# CAN.net
KiCad netlist of a schematic drawn in Altium Designer
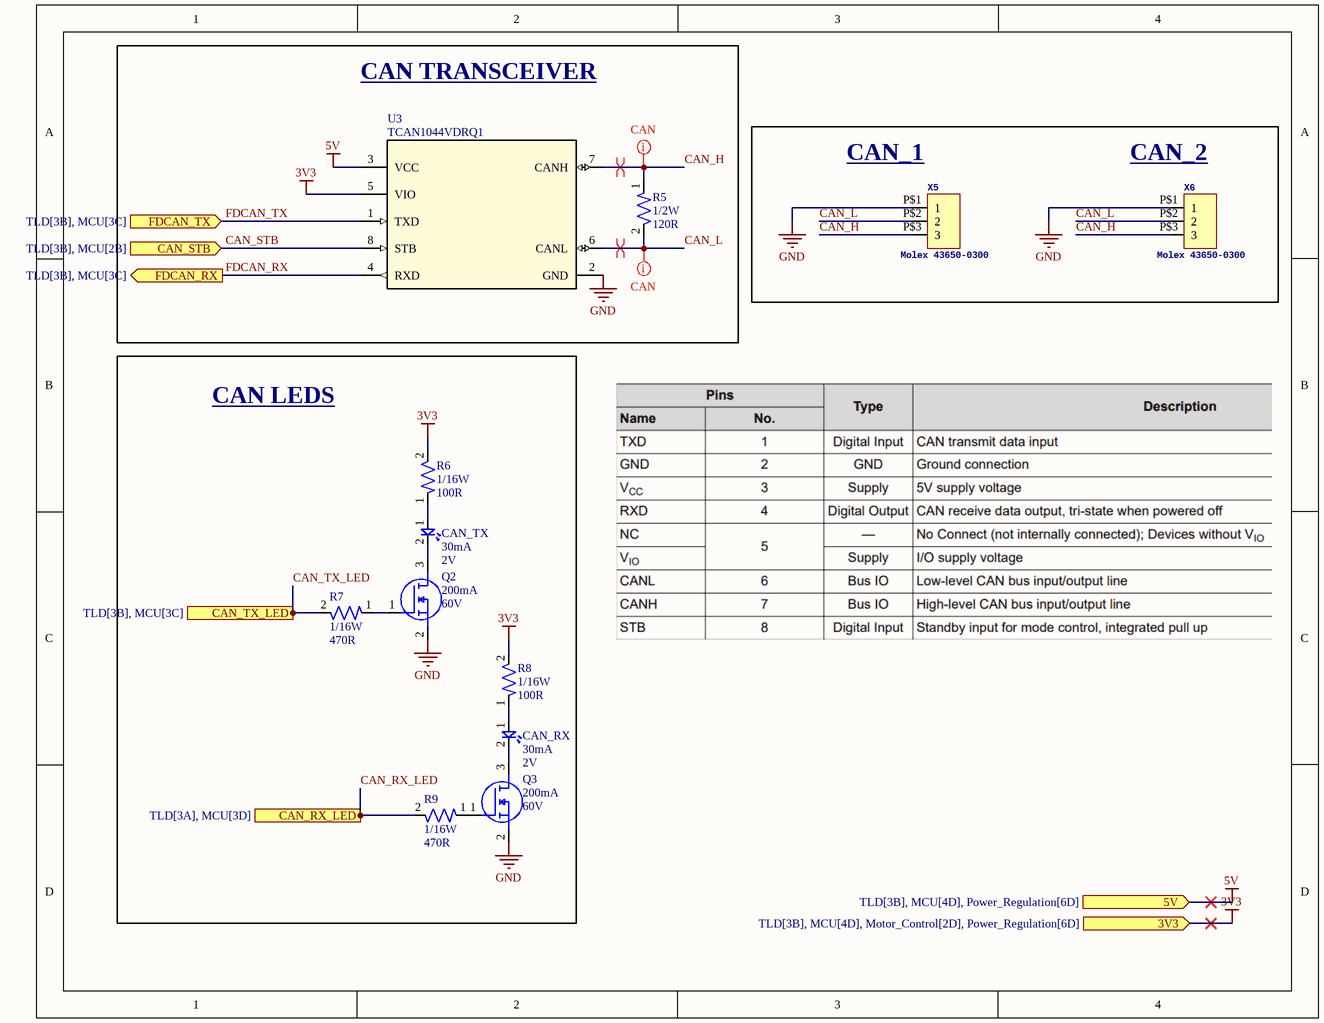
[diagram p0: CAN.SchDoc]

(export (version "E")
  (design (tool "Eeschema 10.0.6"))
  (components
    (comp (ref "CAN_RX")
      (value "BL-HKC36G-AV-TRB")
      (footprint "LED-0603")
      (description "LED YELLOW CLEAR 0603 SMD")
      (fields (field (name "FORWARD CURRENT") "30mA") (field (name "FORWARD VOLTAGE") "2V"))
      (libsource (lib "JLC_25") (part "LED-0001"))
    )
    (comp (ref "CAN_TX")
      (value "BL-HKC36G-AV-TRB")
      (footprint "LED-0603")
      (description "LED YELLOW CLEAR 0603 SMD")
      (fields (field (name "FORWARD CURRENT") "30mA") (field (name "FORWARD VOLTAGE") "2V"))
      (libsource (lib "JLC_25") (part "LED-0001"))
    )
    (comp (ref "Q2")
      (value "T2N7002AK,LM")
      (footprint "IC-SOT23-3")
      (description "MOSFET N-CH 60V 200MA SOT23")
      (fields (field (name "CONTINUOUS CURRENT") "200mA") (field (name "VOLTAGE") "60V"))
      (libsource (lib "JLC_25") (part "NMOS-200MA-0001"))
    )
    (comp (ref "Q3")
      (value "T2N7002AK,LM")
      (footprint "IC-SOT23-3")
      (description "MOSFET N-CH 60V 200MA SOT23")
      (fields (field (name "CONTINUOUS CURRENT") "200mA") (field (name "VOLTAGE") "60V"))
      (libsource (lib "JLC_25") (part "NMOS-200MA-0001"))
    )
    (comp (ref "R5")
      (value "RC1210FR-07120RL")
      (footprint "RES-1210")
      (description "RES 120 OHM 1% 1/2W 1210")
      (fields
        (field (name "TOLERANCE") "1%")
        (field (name "POWER") "1/2W")
        (field (name "RESISTANCE") "120R")
      )
      (libsource (lib "JLC_25") (part "RES-120-0001"))
    )
    (comp (ref "R6")
      (value "RC0402FR-07100RL")
      (footprint "RES-0402")
      (description "RES 100 OHM 1% 1/16W 0402")
      (fields
        (field (name "TOLERANCE") "1%")
        (field (name "POWER") "1/16W")
        (field (name "RESISTANCE") "100R")
      )
      (libsource (lib "JLC_25") (part "RES-100-0001"))
    )
    (comp (ref "R7")
      (value "RC0402FR-07470RL")
      (footprint "RES-0402")
      (description "RES 470 OHM 1% 1/16W 0402")
      (fields
        (field (name "TOLERANCE") "1%")
        (field (name "POWER") "1/16W")
        (field (name "RESISTANCE") "470R")
      )
      (libsource (lib "JLC_25") (part "RES-470-0001"))
    )
    (comp (ref "R8")
      (value "RC0402FR-07100RL")
      (footprint "RES-0402")
      (description "RES 100 OHM 1% 1/16W 0402")
      (fields
        (field (name "TOLERANCE") "1%")
        (field (name "POWER") "1/16W")
        (field (name "RESISTANCE") "100R")
      )
      (libsource (lib "JLC_25") (part "RES-100-0001"))
    )
    (comp (ref "R9")
      (value "RC0402FR-07470RL")
      (footprint "RES-0402")
      (description "RES 470 OHM 1% 1/16W 0402")
      (fields
        (field (name "TOLERANCE") "1%")
        (field (name "POWER") "1/16W")
        (field (name "RESISTANCE") "470R")
      )
      (libsource (lib "JLC_25") (part "RES-470-0001"))
    )
    (comp (ref "U3")
      (value "TCAN1044VDRQ1")
      (footprint "IC-8SOIC")
      (description "IC TRANSCEIVER 1/1 8SOIC")
      (libsource (lib "JLC_25") (part "IC-CAN-0001"))
    )
    (comp (ref "X5")
      (value "Molex 43650-0300")
      (footprint "43650-0300")
      (libsource (lib "Molex Microfit") (part "Micro-Fit Molex 3 Pin Right Angle"))
    )
    (comp (ref "X6")
      (value "Molex 43650-0300")
      (footprint "43650-0300")
      (libsource (lib "Molex Microfit") (part "Micro-Fit Molex 3 Pin Right Angle"))
    )
  )
  (nets
    (net (code "1") (name "/CAN_H") (class "Default")
      (node (ref "R5") (pin "1") (pinfunction "1_1") (pintype "passive"))
      (node (ref "U3") (pin "7") (pinfunction "CANH_7") (pintype "bidirectional"))
      (node (ref "X5") (pin "P$3") (pinfunction "3_P$3") (pintype "passive"))
      (node (ref "X6") (pin "P$3") (pinfunction "3_P$3") (pintype "passive"))
    )
    (net (code "2") (name "/CAN_L") (class "Default")
      (node (ref "R5") (pin "2") (pinfunction "2_2") (pintype "passive"))
      (node (ref "U3") (pin "6") (pinfunction "CANL_6") (pintype "bidirectional"))
      (node (ref "X5") (pin "P$2") (pinfunction "2_P$2") (pintype "passive"))
      (node (ref "X6") (pin "P$2") (pinfunction "2_P$2") (pintype "passive"))
    )
    (net (code "3") (name "/CAN_RX_LED") (class "Default")
      (node (ref "R9") (pin "2") (pinfunction "2_2") (pintype "passive"))
    )
    (net (code "4") (name "/CAN_STB") (class "Default")
      (node (ref "U3") (pin "8") (pinfunction "STB_8") (pintype "input"))
    )
    (net (code "5") (name "/CAN_TX_LED") (class "Default")
      (node (ref "R7") (pin "2") (pinfunction "2_2") (pintype "passive"))
    )
    (net (code "6") (name "/FDCAN_RX") (class "Default")
      (node (ref "U3") (pin "4") (pinfunction "RXD_4") (pintype "output"))
    )
    (net (code "7") (name "/FDCAN_TX") (class "Default")
      (node (ref "U3") (pin "1") (pinfunction "TXD_1") (pintype "input"))
    )
    (net (code "8") (name "3V3") (class "Default")
      (node (ref "R6") (pin "2") (pinfunction "2_2") (pintype "passive"))
      (node (ref "R8") (pin "2") (pinfunction "2_2") (pintype "passive"))
      (node (ref "U3") (pin "5") (pinfunction "VIO_5") (pintype "power_in"))
    )
    (net (code "9") (name "5V") (class "Default")
      (node (ref "U3") (pin "3") (pinfunction "VCC_3") (pintype "power_in"))
    )
    (net (code "10") (name "GND") (class "Default")
      (node (ref "Q2") (pin "2") (pinfunction "S_2") (pintype "passive"))
      (node (ref "Q3") (pin "2") (pinfunction "S_2") (pintype "passive"))
      (node (ref "U3") (pin "2") (pinfunction "GND_2") (pintype "power_in"))
      (node (ref "X5") (pin "P$1") (pinfunction "1_P$1") (pintype "passive"))
      (node (ref "X6") (pin "P$1") (pinfunction "1_P$1") (pintype "passive"))
    )
    (net (code "11") (name "Net-(CAN_RX-Pad1)") (class "Default")
      (node (ref "CAN_RX") (pin "1") (pinfunction "1_1") (pintype "passive"))
      (node (ref "R8") (pin "1") (pinfunction "1_1") (pintype "passive"))
    )
    (net (code "12") (name "Net-(CAN_TX-Pad1)") (class "Default")
      (node (ref "CAN_TX") (pin "1") (pinfunction "1_1") (pintype "passive"))
      (node (ref "R6") (pin "1") (pinfunction "1_1") (pintype "passive"))
    )
    (net (code "13") (name "Net-(Q2-D)") (class "Default")
      (node (ref "CAN_TX") (pin "2") (pinfunction "2_2") (pintype "passive"))
      (node (ref "Q2") (pin "3") (pinfunction "D_3") (pintype "passive"))
    )
    (net (code "14") (name "Net-(Q2-G)") (class "Default")
      (node (ref "Q2") (pin "1") (pinfunction "G_1") (pintype "passive"))
      (node (ref "R7") (pin "1") (pinfunction "1_1") (pintype "passive"))
    )
    (net (code "15") (name "Net-(Q3-D)") (class "Default")
      (node (ref "CAN_RX") (pin "2") (pinfunction "2_2") (pintype "passive"))
      (node (ref "Q3") (pin "3") (pinfunction "D_3") (pintype "passive"))
    )
    (net (code "16") (name "Net-(Q3-G)") (class "Default")
      (node (ref "Q3") (pin "1") (pinfunction "G_1") (pintype "passive"))
      (node (ref "R9") (pin "1") (pinfunction "1_1") (pintype "passive"))
    )
  )
)
